# AVR.net
KiCad netlist of a schematic drawn in Altium Designer
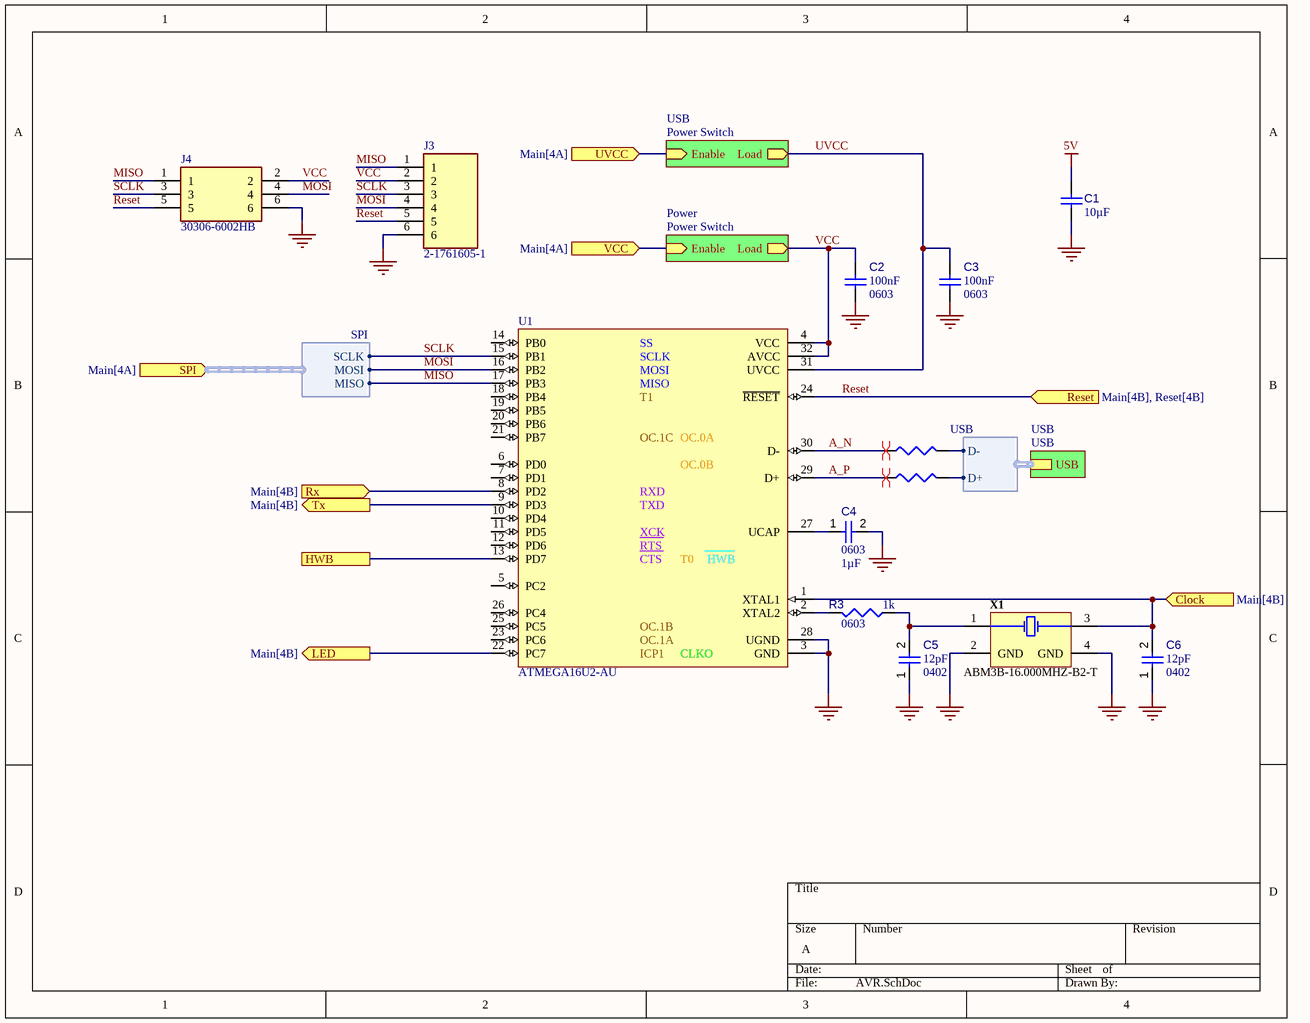
[diagram p0: AVR.SchDoc]

(export (version "E")
  (design (tool "Eeschema 10.0.6"))
  (components
    (comp (ref "C1")
      (value "10µF")
      (footprint "CAPC2013X135X45NL10T25")
      (description "Chip Capacitor, 10 uF, +/- 10%, 16 V, 0805 (2012 Metric)")
      (fields (field (name "TOLERANCE") "10%") (field (name "Comment") "Capacitor 10 uF +/- 10% 16 V 0805"))
      (libsource (lib "Twill Technology Inc") (part "CAP-NP-2"))
    )
    (comp (ref "C2")
      (value "100nF")
      (footprint "CAPC1608X90X40NL10T20")
      (description "Chip Capacitor, 100 nF, +/- 10%, 50 V, 0603 (1608 Metric)")
      (fields
        (field (name "TOLERANCE") "10%")
        (field (name "CASE/PACKAGE") "0603")
        (field (name "Comment") "Capacitor 100 nF +/-10% 50 V 0603")
      )
      (libsource (lib "Twill Technology Inc") (part "CAP-NP-2"))
    )
    (comp (ref "C3")
      (value "100nF")
      (footprint "CAPC1608X90X40NL10T20")
      (description "Chip Capacitor, 100 nF, +/- 10%, 50 V, 0603 (1608 Metric)")
      (fields
        (field (name "TOLERANCE") "10%")
        (field (name "CASE/PACKAGE") "0603")
        (field (name "Comment") "Capacitor 100 nF +/-10% 50 V 0603")
      )
      (libsource (lib "Twill Technology Inc") (part "CAP-NP-2"))
    )
    (comp (ref "C4")
      (value "1µF")
      (footprint "CAPC1608X90X35ML15T15")
      (description "Chip Capacitor, 1 uF, +/- 10%, 16 V, 0603 (1608 Metric)")
      (fields
        (field (name "CASE/PACKAGE") "0603")
        (field (name "TOLERANCE") "10%")
        (field (name "Comment") "Capacitor 1uF +/- 10% 16V 0603")
      )
      (libsource (lib "") (part "CAP-NP-2_1"))
    )
    (comp (ref "C5")
      (value "12pF")
      (footprint "CAPC0402(1005)33_L")
      (description "Chip Capacitor, 12pF +/-10%, 50V, 0402, Thickness 0.33 mm")
      (fields
        (field (name "CASE/PACKAGE") "0402")
        (field (name "TOLERANCE") "20%")
        (field (name "Comment") "Capacitor 12pF +/-10% 50V 0402")
      )
      (libsource (lib "") (part "CAP-NP-2_1"))
    )
    (comp (ref "C6")
      (value "12pF")
      (footprint "CAPC0402(1005)33_L")
      (description "Chip Capacitor, 12pF +/-10%, 50V, 0402, Thickness 0.33 mm")
      (fields
        (field (name "CASE/PACKAGE") "0402")
        (field (name "TOLERANCE") "20%")
        (field (name "Comment") "Capacitor 12pF +/-10% 50V 0402")
      )
      (libsource (lib "") (part "CAP-NP-2_1"))
    )
    (comp (ref "J3")
      (value "2-1761605-1")
      (footprint "TE_2-1761605-1")
      (description "Wire-To-Board Connector, AMP-LATCH Series, Through Hole, Header, 6, 2.54 mm, Gold Plated Contacts")
      (fields (field (name "MF") "TE Connectivity"))
      (libsource (lib "Twill Technology Inc") (part "2-1761605-1"))
    )
    (comp (ref "J4")
      (value "30306-6002HB")
      (footprint "3M_30306-6002HB")
      (description "Connector Header Through Hole 6 position 0.100 _2.54mm_")
      (fields (field (name "MF") "3M"))
      (libsource (lib "Twill Technology Inc") (part "30306-6002HB"))
    )
    (comp (ref "R1")
      (value "Resistor 22R +/-1% 0603 100 mW")
      (footprint "RESC1609X50X30ML08T20")
      (description "Chip Resistor, 22 Ohm, +/- 1%, 100 mW, -55 to 155 degC, 0603 (1608 Metric)")
      (fields (field (name "POWER") "100mW") (field (name "TOLERANCE") "1%"))
      (libsource (lib "Twill Technology Inc") (part "RES-2"))
    )
    (comp (ref "R2")
      (value "Resistor 22R +/-1% 0603 100 mW")
      (footprint "RESC1609X50X30ML08T20")
      (description "Chip Resistor, 22 Ohm, +/- 1%, 100 mW, -55 to 155 degC, 0603 (1608 Metric)")
      (fields (field (name "POWER") "100mW") (field (name "TOLERANCE") "1%"))
      (libsource (lib "Twill Technology Inc") (part "RES-2"))
    )
    (comp (ref "R3")
      (value "1k")
      (footprint "RESC1608X55X25ML10T15")
      (description "Chip Resistor, 1 KOhm, +/-1%, 0.1 W, -55 to 155 degC, 0603 (1608 Metric)")
      (fields
        (field (name "CASE/PACKAGE") "0603")
        (field (name "POWER") "100mW")
        (field (name "TOLERANCE") "1%")
      )
      (libsource (lib "Twill Technology Inc") (part "RES-2"))
    )
    (comp (ref "U1")
      (value "ATMEGA16U2-AU")
      (footprint "QFP80P900X900X120-32N")
      (description "AVR AVR® ATmega Microcontroller IC 8-Bit 16MHz 16KB FLASH 32-TQFP 7x7")
      (fields (field (name "MF") "Microchip") (field (name "DIGI-KEY_PART_NUMBER") "ATMEGA16U2-AU-ND"))
      (libsource (lib "Twill Technology Inc") (part "ATMEGA16U2-AU"))
    )
    (comp (ref "X1")
      (value "ABM3B-16.000MHZ-B2-T")
      (footprint "ABRA-ABM3B-4_V")
      (description "Ceramic SMD Crystal, 16 MHz, +/- 20 ppm, 18 pF, -20 to 70 degC, 4-Pin SMD, RoHS, Tape and Reel")
      (fields (field (name "TOLERANCE") "20ppm") (field (name "MANUFACTURER") "Abracon"))
      (libsource (lib "Twill Technology Inc") (part "XTAL-1-3-4"))
    )
  )
  (nets
    (net (code "3") (name "/A_N") (class "Default")
      (node (ref "R1") (pin "2") (pinfunction "2_2") (pintype "passive"))
      (node (ref "U1") (pin "30") (pinfunction "D-_30") (pintype "bidirectional"))
    )
    (net (code "4") (name "/A_P") (class "Default")
      (node (ref "R2") (pin "2") (pinfunction "2_2") (pintype "passive"))
      (node (ref "U1") (pin "29") (pinfunction "D+_29") (pintype "bidirectional"))
    )
    (net (code "5") (name "/Clock") (class "Default")
      (node (ref "C6") (pin "2") (pinfunction "2_2") (pintype "passive"))
      (node (ref "U1") (pin "1") (pinfunction "XTAL1_1") (pintype "input"))
      (node (ref "X1") (pin "3") (pinfunction "X2_3") (pintype "passive"))
    )
    (net (code "6") (name "/D+") (class "Default")
      (node (ref "R2") (pin "1") (pinfunction "1_1") (pintype "passive"))
    )
    (net (code "7") (name "/D-") (class "Default")
      (node (ref "R1") (pin "1") (pinfunction "1_1") (pintype "passive"))
    )
    (net (code "8") (name "/HWB") (class "Default")
      (node (ref "U1") (pin "13") (pinfunction "PD7_13") (pintype "bidirectional"))
    )
    (net (code "9") (name "/LED") (class "Default")
      (node (ref "U1") (pin "22") (pinfunction "PC7_22") (pintype "bidirectional"))
    )
    (net (code "10") (name "/MISO") (class "Default")
      (node (ref "J3") (pin "1") (pinfunction "1_1") (pintype "passive"))
      (node (ref "J4") (pin "1") (pinfunction "1_1") (pintype "passive"))
      (node (ref "U1") (pin "17") (pinfunction "PB3_17") (pintype "bidirectional"))
    )
    (net (code "11") (name "/MOSI") (class "Default")
      (node (ref "J3") (pin "4") (pinfunction "4_4") (pintype "passive"))
      (node (ref "J4") (pin "4") (pinfunction "4_4") (pintype "passive"))
      (node (ref "U1") (pin "16") (pinfunction "PB2_16") (pintype "bidirectional"))
    )
    (net (code "12") (name "/Reset") (class "Default")
      (node (ref "J3") (pin "5") (pinfunction "5_5") (pintype "passive"))
      (node (ref "J4") (pin "5") (pinfunction "5_5") (pintype "passive"))
      (node (ref "U1") (pin "24") (pinfunction "~{RESET}_24") (pintype "bidirectional"))
    )
    (net (code "13") (name "/Rx") (class "Default")
      (node (ref "U1") (pin "8") (pinfunction "PD2_8") (pintype "bidirectional"))
    )
    (net (code "14") (name "/SCLK") (class "Default")
      (node (ref "J3") (pin "3") (pinfunction "3_3") (pintype "passive"))
      (node (ref "J4") (pin "3") (pinfunction "3_3") (pintype "passive"))
      (node (ref "U1") (pin "15") (pinfunction "PB1_15") (pintype "bidirectional"))
    )
    (net (code "15") (name "/Tx") (class "Default")
      (node (ref "U1") (pin "9") (pinfunction "PD3_9") (pintype "bidirectional"))
    )
    (net (code "16") (name "/UVCC") (class "Default")
      (node (ref "C3") (pin "2") (pinfunction "2_2") (pintype "passive"))
      (node (ref "U1") (pin "31") (pinfunction "UVCC_31") (pintype "power_in"))
    )
    (net (code "17") (name "/VCC") (class "Default")
      (node (ref "C2") (pin "2") (pinfunction "2_2") (pintype "passive"))
      (node (ref "J3") (pin "2") (pinfunction "2_2") (pintype "passive"))
      (node (ref "J4") (pin "2") (pinfunction "2_2") (pintype "passive"))
      (node (ref "U1") (pin "32") (pinfunction "AVCC_32") (pintype "power_in"))
      (node (ref "U1") (pin "4") (pinfunction "VCC_4") (pintype "power_in"))
    )
    (net (code "20") (name "5V") (class "Default")
      (node (ref "C1") (pin "1") (pinfunction "1_1") (pintype "passive"))
    )
    (net (code "21") (name "GND") (class "Default")
      (node (ref "C1") (pin "2") (pinfunction "2_2") (pintype "passive"))
      (node (ref "C2") (pin "1") (pinfunction "1_1") (pintype "passive"))
      (node (ref "C3") (pin "1") (pinfunction "1_1") (pintype "passive"))
      (node (ref "C4") (pin "2") (pinfunction "2_2") (pintype "passive"))
      (node (ref "C5") (pin "1") (pinfunction "1_1") (pintype "passive"))
      (node (ref "C6") (pin "1") (pinfunction "1_1") (pintype "passive"))
      (node (ref "J3") (pin "6") (pinfunction "6_6") (pintype "passive"))
      (node (ref "J4") (pin "6") (pinfunction "6_6") (pintype "passive"))
      (node (ref "U1") (pin "28") (pinfunction "UGND_28") (pintype "power_in"))
      (node (ref "U1") (pin "3") (pinfunction "GND_3") (pintype "power_in"))
      (node (ref "X1") (pin "2") (pinfunction "GND_2") (pintype "power_in"))
      (node (ref "X1") (pin "4") (pinfunction "GND_4") (pintype "power_in"))
    )
    (net (code "22") (name "Net-(U1-UCAP)") (class "Default")
      (node (ref "C4") (pin "1") (pinfunction "1_1") (pintype "passive"))
      (node (ref "U1") (pin "27") (pinfunction "UCAP_27") (pintype "power_in"))
    )
    (net (code "23") (name "Net-(U1-XTAL2)") (class "Default")
      (node (ref "R3") (pin "2") (pinfunction "2_2") (pintype "passive"))
      (node (ref "U1") (pin "2") (pinfunction "XTAL2_2") (pintype "bidirectional"))
    )
    (net (code "24") (name "Net-(X1-X1)") (class "Default")
      (node (ref "C5") (pin "2") (pinfunction "2_2") (pintype "passive"))
      (node (ref "R3") (pin "1") (pinfunction "1_1") (pintype "passive"))
      (node (ref "X1") (pin "1") (pinfunction "X1_1") (pintype "passive"))
    )
    (net (code "25") (name "unconnected-(U1-PB0-Pad14)") (class "Default")
      (node (ref "U1") (pin "14") (pinfunction "PB0_14") (pintype "bidirectional"))
    )
    (net (code "26") (name "unconnected-(U1-PB4-Pad18)") (class "Default")
      (node (ref "U1") (pin "18") (pinfunction "PB4_18") (pintype "bidirectional"))
    )
    (net (code "27") (name "unconnected-(U1-PB5-Pad19)") (class "Default")
      (node (ref "U1") (pin "19") (pinfunction "PB5_19") (pintype "bidirectional"))
    )
    (net (code "28") (name "unconnected-(U1-PB6-Pad20)") (class "Default")
      (node (ref "U1") (pin "20") (pinfunction "PB6_20") (pintype "bidirectional"))
    )
    (net (code "29") (name "unconnected-(U1-PB7-Pad21)") (class "Default")
      (node (ref "U1") (pin "21") (pinfunction "PB7_21") (pintype "bidirectional"))
    )
    (net (code "30") (name "unconnected-(U1-PC2-Pad5)") (class "Default")
      (node (ref "U1") (pin "5") (pinfunction "PC2_5") (pintype "bidirectional"))
    )
    (net (code "31") (name "unconnected-(U1-PC4-Pad26)") (class "Default")
      (node (ref "U1") (pin "26") (pinfunction "PC4_26") (pintype "bidirectional"))
    )
    (net (code "32") (name "unconnected-(U1-PC5-Pad25)") (class "Default")
      (node (ref "U1") (pin "25") (pinfunction "PC5_25") (pintype "bidirectional"))
    )
    (net (code "33") (name "unconnected-(U1-PC6-Pad23)") (class "Default")
      (node (ref "U1") (pin "23") (pinfunction "PC6_23") (pintype "bidirectional"))
    )
    (net (code "34") (name "unconnected-(U1-PD0-Pad6)") (class "Default")
      (node (ref "U1") (pin "6") (pinfunction "PD0_6") (pintype "bidirectional"))
    )
    (net (code "35") (name "unconnected-(U1-PD1-Pad7)") (class "Default")
      (node (ref "U1") (pin "7") (pinfunction "PD1_7") (pintype "bidirectional"))
    )
    (net (code "36") (name "unconnected-(U1-PD4-Pad10)") (class "Default")
      (node (ref "U1") (pin "10") (pinfunction "PD4_10") (pintype "bidirectional"))
    )
    (net (code "37") (name "unconnected-(U1-PD5-Pad11)") (class "Default")
      (node (ref "U1") (pin "11") (pinfunction "PD5_11") (pintype "bidirectional"))
    )
    (net (code "38") (name "unconnected-(U1-PD6-Pad12)") (class "Default")
      (node (ref "U1") (pin "12") (pinfunction "PD6_12") (pintype "bidirectional"))
    )
  )
)
